# ethernet_switch.net
KiCad netlist of a schematic drawn in EAGLE
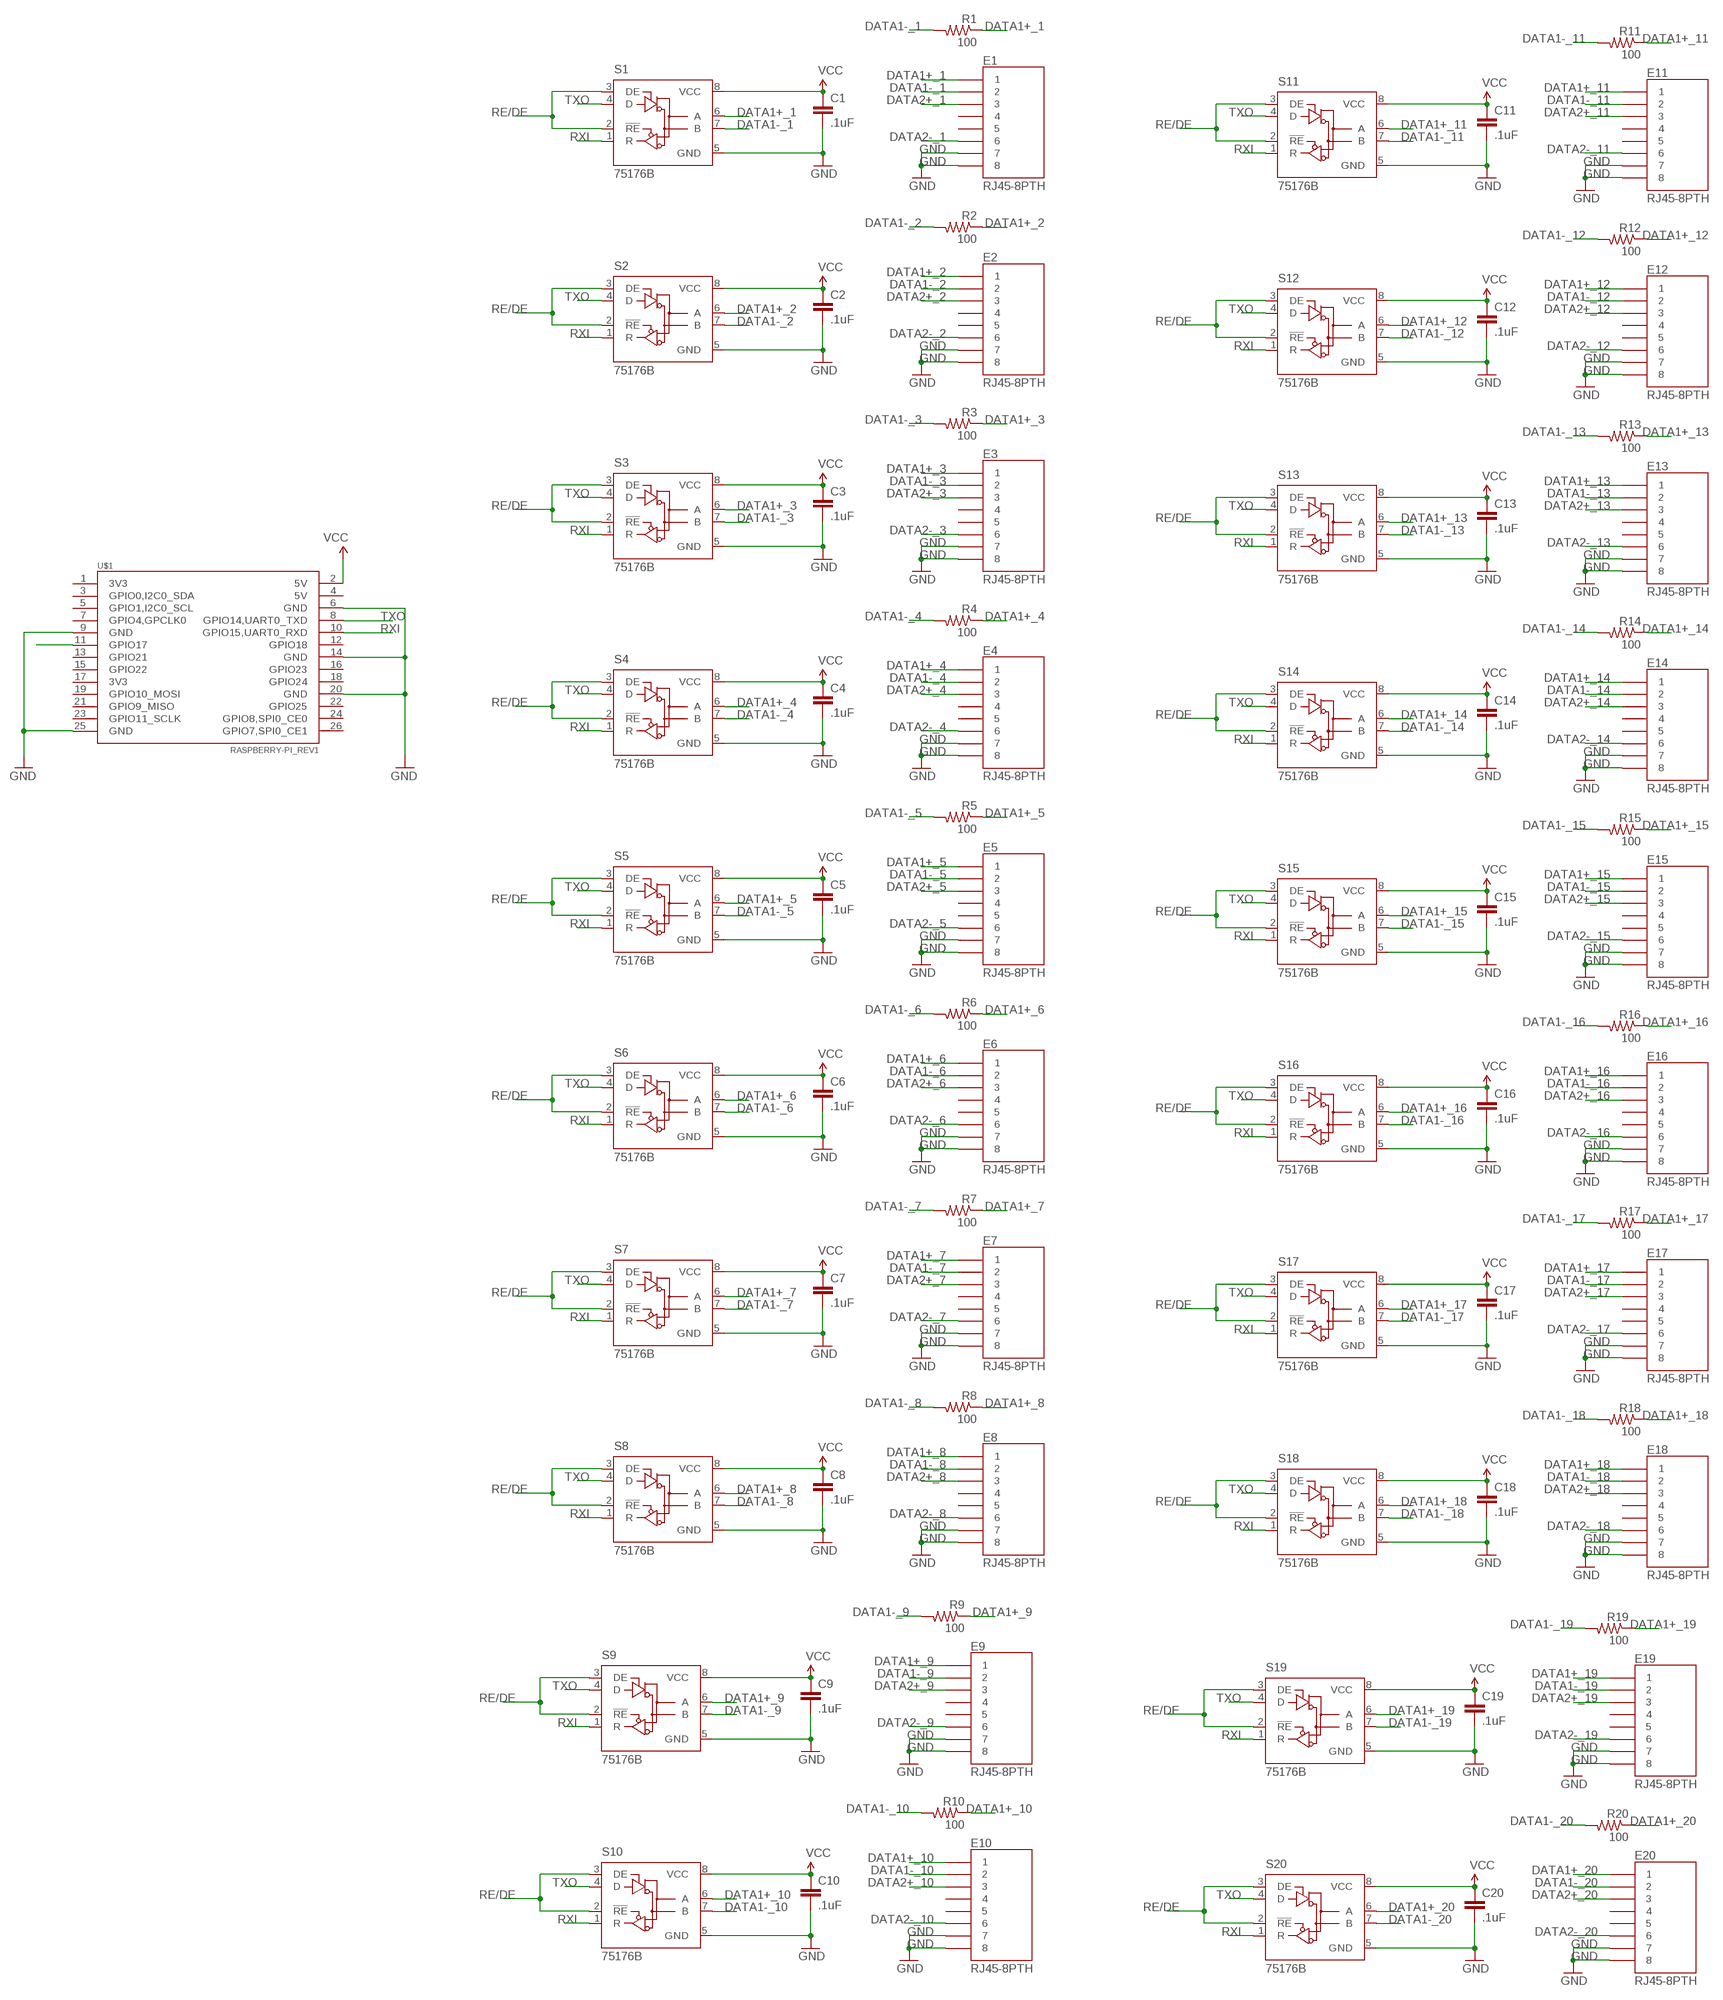
[diagram p0: schematic, sheet 1]

(export (version "E")
  (design (tool "Eeschema 10.0.6"))
  (components
    (comp (ref "C1")
      (value ".1uF")
      (footprint "eagle-import:0402-CAP")
      (libsource (lib "eagle-import") (part "CAP0402-CAP"))
    )
    (comp (ref "C2")
      (value ".1uF")
      (footprint "eagle-import:0402-CAP")
      (libsource (lib "eagle-import") (part "CAP0402-CAP"))
    )
    (comp (ref "C3")
      (value ".1uF")
      (footprint "eagle-import:0402-CAP")
      (libsource (lib "eagle-import") (part "CAP0402-CAP"))
    )
    (comp (ref "C4")
      (value ".1uF")
      (footprint "eagle-import:0402-CAP")
      (libsource (lib "eagle-import") (part "CAP0402-CAP"))
    )
    (comp (ref "C5")
      (value ".1uF")
      (footprint "eagle-import:0402-CAP")
      (libsource (lib "eagle-import") (part "CAP0402-CAP"))
    )
    (comp (ref "C6")
      (value ".1uF")
      (footprint "eagle-import:0402-CAP")
      (libsource (lib "eagle-import") (part "CAP0402-CAP"))
    )
    (comp (ref "C7")
      (value ".1uF")
      (footprint "eagle-import:0402-CAP")
      (libsource (lib "eagle-import") (part "CAP0402-CAP"))
    )
    (comp (ref "C8")
      (value ".1uF")
      (footprint "eagle-import:0402-CAP")
      (libsource (lib "eagle-import") (part "CAP0402-CAP"))
    )
    (comp (ref "C9")
      (value ".1uF")
      (footprint "eagle-import:0402-CAP")
      (libsource (lib "eagle-import") (part "CAP0402-CAP"))
    )
    (comp (ref "C10")
      (value ".1uF")
      (footprint "eagle-import:0402-CAP")
      (libsource (lib "eagle-import") (part "CAP0402-CAP"))
    )
    (comp (ref "C11")
      (value ".1uF")
      (footprint "eagle-import:0402-CAP")
      (libsource (lib "eagle-import") (part "CAP0402-CAP"))
    )
    (comp (ref "C12")
      (value ".1uF")
      (footprint "eagle-import:0402-CAP")
      (libsource (lib "eagle-import") (part "CAP0402-CAP"))
    )
    (comp (ref "C13")
      (value ".1uF")
      (footprint "eagle-import:0402-CAP")
      (libsource (lib "eagle-import") (part "CAP0402-CAP"))
    )
    (comp (ref "C14")
      (value ".1uF")
      (footprint "eagle-import:0402-CAP")
      (libsource (lib "eagle-import") (part "CAP0402-CAP"))
    )
    (comp (ref "C15")
      (value ".1uF")
      (footprint "eagle-import:0402-CAP")
      (libsource (lib "eagle-import") (part "CAP0402-CAP"))
    )
    (comp (ref "C16")
      (value ".1uF")
      (footprint "eagle-import:0402-CAP")
      (libsource (lib "eagle-import") (part "CAP0402-CAP"))
    )
    (comp (ref "C17")
      (value ".1uF")
      (footprint "eagle-import:0402-CAP")
      (libsource (lib "eagle-import") (part "CAP0402-CAP"))
    )
    (comp (ref "C18")
      (value ".1uF")
      (footprint "eagle-import:0402-CAP")
      (libsource (lib "eagle-import") (part "CAP0402-CAP"))
    )
    (comp (ref "C19")
      (value ".1uF")
      (footprint "eagle-import:0402-CAP")
      (libsource (lib "eagle-import") (part "CAP0402-CAP"))
    )
    (comp (ref "C20")
      (value ".1uF")
      (footprint "eagle-import:0402-CAP")
      (libsource (lib "eagle-import") (part "CAP0402-CAP"))
    )
    (comp (ref "E1")
      (value "RJ45-8PTH")
      (footprint "eagle-import:RJ45-8")
      (libsource (lib "eagle-import") (part "RJ45-8PTH"))
    )
    (comp (ref "E2")
      (value "RJ45-8PTH")
      (footprint "eagle-import:RJ45-8")
      (libsource (lib "eagle-import") (part "RJ45-8PTH"))
    )
    (comp (ref "E3")
      (value "RJ45-8PTH")
      (footprint "eagle-import:RJ45-8")
      (libsource (lib "eagle-import") (part "RJ45-8PTH"))
    )
    (comp (ref "E4")
      (value "RJ45-8PTH")
      (footprint "eagle-import:RJ45-8")
      (libsource (lib "eagle-import") (part "RJ45-8PTH"))
    )
    (comp (ref "E5")
      (value "RJ45-8PTH")
      (footprint "eagle-import:RJ45-8")
      (libsource (lib "eagle-import") (part "RJ45-8PTH"))
    )
    (comp (ref "E6")
      (value "RJ45-8PTH")
      (footprint "eagle-import:RJ45-8")
      (libsource (lib "eagle-import") (part "RJ45-8PTH"))
    )
    (comp (ref "E7")
      (value "RJ45-8PTH")
      (footprint "eagle-import:RJ45-8")
      (libsource (lib "eagle-import") (part "RJ45-8PTH"))
    )
    (comp (ref "E8")
      (value "RJ45-8PTH")
      (footprint "eagle-import:RJ45-8")
      (libsource (lib "eagle-import") (part "RJ45-8PTH"))
    )
    (comp (ref "E9")
      (value "RJ45-8PTH")
      (footprint "eagle-import:RJ45-8")
      (libsource (lib "eagle-import") (part "RJ45-8PTH"))
    )
    (comp (ref "E10")
      (value "RJ45-8PTH")
      (footprint "eagle-import:RJ45-8")
      (libsource (lib "eagle-import") (part "RJ45-8PTH"))
    )
    (comp (ref "E11")
      (value "RJ45-8PTH")
      (footprint "eagle-import:RJ45-8")
      (libsource (lib "eagle-import") (part "RJ45-8PTH"))
    )
    (comp (ref "E12")
      (value "RJ45-8PTH")
      (footprint "eagle-import:RJ45-8")
      (libsource (lib "eagle-import") (part "RJ45-8PTH"))
    )
    (comp (ref "E13")
      (value "RJ45-8PTH")
      (footprint "eagle-import:RJ45-8")
      (libsource (lib "eagle-import") (part "RJ45-8PTH"))
    )
    (comp (ref "E14")
      (value "RJ45-8PTH")
      (footprint "eagle-import:RJ45-8")
      (libsource (lib "eagle-import") (part "RJ45-8PTH"))
    )
    (comp (ref "E15")
      (value "RJ45-8PTH")
      (footprint "eagle-import:RJ45-8")
      (libsource (lib "eagle-import") (part "RJ45-8PTH"))
    )
    (comp (ref "E16")
      (value "RJ45-8PTH")
      (footprint "eagle-import:RJ45-8")
      (libsource (lib "eagle-import") (part "RJ45-8PTH"))
    )
    (comp (ref "E17")
      (value "RJ45-8PTH")
      (footprint "eagle-import:RJ45-8")
      (libsource (lib "eagle-import") (part "RJ45-8PTH"))
    )
    (comp (ref "E18")
      (value "RJ45-8PTH")
      (footprint "eagle-import:RJ45-8")
      (libsource (lib "eagle-import") (part "RJ45-8PTH"))
    )
    (comp (ref "E19")
      (value "RJ45-8PTH")
      (footprint "eagle-import:RJ45-8")
      (libsource (lib "eagle-import") (part "RJ45-8PTH"))
    )
    (comp (ref "E20")
      (value "RJ45-8PTH")
      (footprint "eagle-import:RJ45-8")
      (libsource (lib "eagle-import") (part "RJ45-8PTH"))
    )
    (comp (ref "R1")
      (value "100")
      (footprint "eagle-import:1206")
      (libsource (lib "eagle-import") (part "RESISTOR1206"))
    )
    (comp (ref "R2")
      (value "100")
      (footprint "eagle-import:1206")
      (libsource (lib "eagle-import") (part "RESISTOR1206"))
    )
    (comp (ref "R3")
      (value "100")
      (footprint "eagle-import:1206")
      (libsource (lib "eagle-import") (part "RESISTOR1206"))
    )
    (comp (ref "R4")
      (value "100")
      (footprint "eagle-import:1206")
      (libsource (lib "eagle-import") (part "RESISTOR1206"))
    )
    (comp (ref "R5")
      (value "100")
      (footprint "eagle-import:1206")
      (libsource (lib "eagle-import") (part "RESISTOR1206"))
    )
    (comp (ref "R6")
      (value "100")
      (footprint "eagle-import:1206")
      (libsource (lib "eagle-import") (part "RESISTOR1206"))
    )
    (comp (ref "R7")
      (value "100")
      (footprint "eagle-import:1206")
      (libsource (lib "eagle-import") (part "RESISTOR1206"))
    )
    (comp (ref "R8")
      (value "100")
      (footprint "eagle-import:1206")
      (libsource (lib "eagle-import") (part "RESISTOR1206"))
    )
    (comp (ref "R9")
      (value "100")
      (footprint "eagle-import:1206")
      (libsource (lib "eagle-import") (part "RESISTOR1206"))
    )
    (comp (ref "R10")
      (value "100")
      (footprint "eagle-import:1206")
      (libsource (lib "eagle-import") (part "RESISTOR1206"))
    )
    (comp (ref "R11")
      (value "100")
      (footprint "eagle-import:1206")
      (libsource (lib "eagle-import") (part "RESISTOR1206"))
    )
    (comp (ref "R12")
      (value "100")
      (footprint "eagle-import:1206")
      (libsource (lib "eagle-import") (part "RESISTOR1206"))
    )
    (comp (ref "R13")
      (value "100")
      (footprint "eagle-import:1206")
      (libsource (lib "eagle-import") (part "RESISTOR1206"))
    )
    (comp (ref "R14")
      (value "100")
      (footprint "eagle-import:1206")
      (libsource (lib "eagle-import") (part "RESISTOR1206"))
    )
    (comp (ref "R15")
      (value "100")
      (footprint "eagle-import:1206")
      (libsource (lib "eagle-import") (part "RESISTOR1206"))
    )
    (comp (ref "R16")
      (value "100")
      (footprint "eagle-import:1206")
      (libsource (lib "eagle-import") (part "RESISTOR1206"))
    )
    (comp (ref "R17")
      (value "100")
      (footprint "eagle-import:1206")
      (libsource (lib "eagle-import") (part "RESISTOR1206"))
    )
    (comp (ref "R18")
      (value "100")
      (footprint "eagle-import:1206")
      (libsource (lib "eagle-import") (part "RESISTOR1206"))
    )
    (comp (ref "R19")
      (value "100")
      (footprint "eagle-import:1206")
      (libsource (lib "eagle-import") (part "RESISTOR1206"))
    )
    (comp (ref "R20")
      (value "100")
      (footprint "eagle-import:1206")
      (libsource (lib "eagle-import") (part "RESISTOR1206"))
    )
    (comp (ref "S1")
      (value "75176B")
      (footprint "eagle-import:D_R-PDSO-G8")
      (libsource (lib "eagle-import") (part "75176B"))
    )
    (comp (ref "S2")
      (value "75176B")
      (footprint "eagle-import:D_R-PDSO-G8")
      (libsource (lib "eagle-import") (part "75176B"))
    )
    (comp (ref "S3")
      (value "75176B")
      (footprint "eagle-import:D_R-PDSO-G8")
      (libsource (lib "eagle-import") (part "75176B"))
    )
    (comp (ref "S4")
      (value "75176B")
      (footprint "eagle-import:D_R-PDSO-G8")
      (libsource (lib "eagle-import") (part "75176B"))
    )
    (comp (ref "S5")
      (value "75176B")
      (footprint "eagle-import:D_R-PDSO-G8")
      (libsource (lib "eagle-import") (part "75176B"))
    )
    (comp (ref "S6")
      (value "75176B")
      (footprint "eagle-import:D_R-PDSO-G8")
      (libsource (lib "eagle-import") (part "75176B"))
    )
    (comp (ref "S7")
      (value "75176B")
      (footprint "eagle-import:D_R-PDSO-G8")
      (libsource (lib "eagle-import") (part "75176B"))
    )
    (comp (ref "S8")
      (value "75176B")
      (footprint "eagle-import:D_R-PDSO-G8")
      (libsource (lib "eagle-import") (part "75176B"))
    )
    (comp (ref "S9")
      (value "75176B")
      (footprint "eagle-import:D_R-PDSO-G8")
      (libsource (lib "eagle-import") (part "75176B"))
    )
    (comp (ref "S10")
      (value "75176B")
      (footprint "eagle-import:D_R-PDSO-G8")
      (libsource (lib "eagle-import") (part "75176B"))
    )
    (comp (ref "S11")
      (value "75176B")
      (footprint "eagle-import:D_R-PDSO-G8")
      (libsource (lib "eagle-import") (part "75176B"))
    )
    (comp (ref "S12")
      (value "75176B")
      (footprint "eagle-import:D_R-PDSO-G8")
      (libsource (lib "eagle-import") (part "75176B"))
    )
    (comp (ref "S13")
      (value "75176B")
      (footprint "eagle-import:D_R-PDSO-G8")
      (libsource (lib "eagle-import") (part "75176B"))
    )
    (comp (ref "S14")
      (value "75176B")
      (footprint "eagle-import:D_R-PDSO-G8")
      (libsource (lib "eagle-import") (part "75176B"))
    )
    (comp (ref "S15")
      (value "75176B")
      (footprint "eagle-import:D_R-PDSO-G8")
      (libsource (lib "eagle-import") (part "75176B"))
    )
    (comp (ref "S16")
      (value "75176B")
      (footprint "eagle-import:D_R-PDSO-G8")
      (libsource (lib "eagle-import") (part "75176B"))
    )
    (comp (ref "S17")
      (value "75176B")
      (footprint "eagle-import:D_R-PDSO-G8")
      (libsource (lib "eagle-import") (part "75176B"))
    )
    (comp (ref "S18")
      (value "75176B")
      (footprint "eagle-import:D_R-PDSO-G8")
      (libsource (lib "eagle-import") (part "75176B"))
    )
    (comp (ref "S19")
      (value "75176B")
      (footprint "eagle-import:D_R-PDSO-G8")
      (libsource (lib "eagle-import") (part "75176B"))
    )
    (comp (ref "S20")
      (value "75176B")
      (footprint "eagle-import:D_R-PDSO-G8")
      (libsource (lib "eagle-import") (part "75176B"))
    )
    (comp (ref "U$1")
      (value "RASPBERRY-PI_REV1")
      (footprint "eagle-import:RASPBERRY-PI_REV1")
      (libsource (lib "eagle-import") (part "RASPBERRY-PI_REV1"))
    )
  )
  (nets
    (net (code "1") (name "/DATA1+_1") (class "Default")
      (node (ref "E1") (pin "1") (pinfunction "1_1") (pintype "bidirectional"))
      (node (ref "R1") (pin "1") (pinfunction "1_1") (pintype "passive"))
      (node (ref "S1") (pin "6") (pinfunction "A_6") (pintype "output"))
    )
    (net (code "2") (name "/DATA1+_2") (class "Default")
      (node (ref "E2") (pin "1") (pinfunction "1_1") (pintype "bidirectional"))
      (node (ref "R2") (pin "1") (pinfunction "1_1") (pintype "passive"))
      (node (ref "S2") (pin "6") (pinfunction "A_6") (pintype "output"))
    )
    (net (code "3") (name "/DATA1+_3") (class "Default")
      (node (ref "E3") (pin "1") (pinfunction "1_1") (pintype "bidirectional"))
      (node (ref "R3") (pin "1") (pinfunction "1_1") (pintype "passive"))
      (node (ref "S3") (pin "6") (pinfunction "A_6") (pintype "output"))
    )
    (net (code "4") (name "/DATA1+_4") (class "Default")
      (node (ref "E4") (pin "1") (pinfunction "1_1") (pintype "bidirectional"))
      (node (ref "R4") (pin "1") (pinfunction "1_1") (pintype "passive"))
      (node (ref "S4") (pin "6") (pinfunction "A_6") (pintype "output"))
    )
    (net (code "5") (name "/DATA1+_5") (class "Default")
      (node (ref "E5") (pin "1") (pinfunction "1_1") (pintype "bidirectional"))
      (node (ref "R5") (pin "1") (pinfunction "1_1") (pintype "passive"))
      (node (ref "S5") (pin "6") (pinfunction "A_6") (pintype "output"))
    )
    (net (code "6") (name "/DATA1+_6") (class "Default")
      (node (ref "E6") (pin "1") (pinfunction "1_1") (pintype "bidirectional"))
      (node (ref "R6") (pin "1") (pinfunction "1_1") (pintype "passive"))
      (node (ref "S6") (pin "6") (pinfunction "A_6") (pintype "output"))
    )
    (net (code "7") (name "/DATA1+_7") (class "Default")
      (node (ref "E7") (pin "1") (pinfunction "1_1") (pintype "bidirectional"))
      (node (ref "R7") (pin "1") (pinfunction "1_1") (pintype "passive"))
      (node (ref "S7") (pin "6") (pinfunction "A_6") (pintype "output"))
    )
    (net (code "8") (name "/DATA1+_8") (class "Default")
      (node (ref "E8") (pin "1") (pinfunction "1_1") (pintype "bidirectional"))
      (node (ref "R8") (pin "1") (pinfunction "1_1") (pintype "passive"))
      (node (ref "S8") (pin "6") (pinfunction "A_6") (pintype "output"))
    )
    (net (code "9") (name "/DATA1+_9") (class "Default")
      (node (ref "E9") (pin "1") (pinfunction "1_1") (pintype "bidirectional"))
      (node (ref "R9") (pin "1") (pinfunction "1_1") (pintype "passive"))
      (node (ref "S9") (pin "6") (pinfunction "A_6") (pintype "output"))
    )
    (net (code "10") (name "/DATA1+_10") (class "Default")
      (node (ref "E10") (pin "1") (pinfunction "1_1") (pintype "bidirectional"))
      (node (ref "R10") (pin "1") (pinfunction "1_1") (pintype "passive"))
      (node (ref "S10") (pin "6") (pinfunction "A_6") (pintype "output"))
    )
    (net (code "11") (name "/DATA1+_11") (class "Default")
      (node (ref "E11") (pin "1") (pinfunction "1_1") (pintype "bidirectional"))
      (node (ref "R11") (pin "1") (pinfunction "1_1") (pintype "passive"))
      (node (ref "S11") (pin "6") (pinfunction "A_6") (pintype "output"))
    )
    (net (code "12") (name "/DATA1+_12") (class "Default")
      (node (ref "E12") (pin "1") (pinfunction "1_1") (pintype "bidirectional"))
      (node (ref "R12") (pin "1") (pinfunction "1_1") (pintype "passive"))
      (node (ref "S12") (pin "6") (pinfunction "A_6") (pintype "output"))
    )
    (net (code "13") (name "/DATA1+_13") (class "Default")
      (node (ref "E13") (pin "1") (pinfunction "1_1") (pintype "bidirectional"))
      (node (ref "R13") (pin "1") (pinfunction "1_1") (pintype "passive"))
      (node (ref "S13") (pin "6") (pinfunction "A_6") (pintype "output"))
    )
    (net (code "14") (name "/DATA1+_14") (class "Default")
      (node (ref "E14") (pin "1") (pinfunction "1_1") (pintype "bidirectional"))
      (node (ref "R14") (pin "1") (pinfunction "1_1") (pintype "passive"))
      (node (ref "S14") (pin "6") (pinfunction "A_6") (pintype "output"))
    )
    (net (code "15") (name "/DATA1+_15") (class "Default")
      (node (ref "E15") (pin "1") (pinfunction "1_1") (pintype "bidirectional"))
      (node (ref "R15") (pin "1") (pinfunction "1_1") (pintype "passive"))
      (node (ref "S15") (pin "6") (pinfunction "A_6") (pintype "output"))
    )
    (net (code "16") (name "/DATA1+_16") (class "Default")
      (node (ref "E16") (pin "1") (pinfunction "1_1") (pintype "bidirectional"))
      (node (ref "R16") (pin "1") (pinfunction "1_1") (pintype "passive"))
      (node (ref "S16") (pin "6") (pinfunction "A_6") (pintype "output"))
    )
    (net (code "17") (name "/DATA1+_17") (class "Default")
      (node (ref "E17") (pin "1") (pinfunction "1_1") (pintype "bidirectional"))
      (node (ref "R17") (pin "1") (pinfunction "1_1") (pintype "passive"))
      (node (ref "S17") (pin "6") (pinfunction "A_6") (pintype "output"))
    )
    (net (code "18") (name "/DATA1+_18") (class "Default")
      (node (ref "E18") (pin "1") (pinfunction "1_1") (pintype "bidirectional"))
      (node (ref "R18") (pin "1") (pinfunction "1_1") (pintype "passive"))
      (node (ref "S18") (pin "6") (pinfunction "A_6") (pintype "output"))
    )
    (net (code "19") (name "/DATA1+_19") (class "Default")
      (node (ref "E19") (pin "1") (pinfunction "1_1") (pintype "bidirectional"))
      (node (ref "R19") (pin "1") (pinfunction "1_1") (pintype "passive"))
      (node (ref "S19") (pin "6") (pinfunction "A_6") (pintype "output"))
    )
    (net (code "20") (name "/DATA1+_20") (class "Default")
      (node (ref "E20") (pin "1") (pinfunction "1_1") (pintype "bidirectional"))
      (node (ref "R20") (pin "1") (pinfunction "1_1") (pintype "passive"))
      (node (ref "S20") (pin "6") (pinfunction "A_6") (pintype "output"))
    )
    (net (code "21") (name "/DATA1-_1") (class "Default")
      (node (ref "E1") (pin "2") (pinfunction "2_2") (pintype "bidirectional"))
      (node (ref "R1") (pin "2") (pinfunction "2_2") (pintype "passive"))
      (node (ref "S1") (pin "7") (pinfunction "B_7") (pintype "output"))
    )
    (net (code "22") (name "/DATA1-_2") (class "Default")
      (node (ref "E2") (pin "2") (pinfunction "2_2") (pintype "bidirectional"))
      (node (ref "R2") (pin "2") (pinfunction "2_2") (pintype "passive"))
      (node (ref "S2") (pin "7") (pinfunction "B_7") (pintype "output"))
    )
    (net (code "23") (name "/DATA1-_3") (class "Default")
      (node (ref "E3") (pin "2") (pinfunction "2_2") (pintype "bidirectional"))
      (node (ref "R3") (pin "2") (pinfunction "2_2") (pintype "passive"))
      (node (ref "S3") (pin "7") (pinfunction "B_7") (pintype "output"))
    )
    (net (code "24") (name "/DATA1-_4") (class "Default")
      (node (ref "E4") (pin "2") (pinfunction "2_2") (pintype "bidirectional"))
      (node (ref "R4") (pin "2") (pinfunction "2_2") (pintype "passive"))
      (node (ref "S4") (pin "7") (pinfunction "B_7") (pintype "output"))
    )
    (net (code "25") (name "/DATA1-_5") (class "Default")
      (node (ref "E5") (pin "2") (pinfunction "2_2") (pintype "bidirectional"))
      (node (ref "R5") (pin "2") (pinfunction "2_2") (pintype "passive"))
      (node (ref "S5") (pin "7") (pinfunction "B_7") (pintype "output"))
    )
    (net (code "26") (name "/DATA1-_6") (class "Default")
      (node (ref "E6") (pin "2") (pinfunction "2_2") (pintype "bidirectional"))
      (node (ref "R6") (pin "2") (pinfunction "2_2") (pintype "passive"))
      (node (ref "S6") (pin "7") (pinfunction "B_7") (pintype "output"))
    )
    (net (code "27") (name "/DATA1-_7") (class "Default")
      (node (ref "E7") (pin "2") (pinfunction "2_2") (pintype "bidirectional"))
      (node (ref "R7") (pin "2") (pinfunction "2_2") (pintype "passive"))
      (node (ref "S7") (pin "7") (pinfunction "B_7") (pintype "output"))
    )
    (net (code "28") (name "/DATA1-_8") (class "Default")
      (node (ref "E8") (pin "2") (pinfunction "2_2") (pintype "bidirectional"))
      (node (ref "R8") (pin "2") (pinfunction "2_2") (pintype "passive"))
      (node (ref "S8") (pin "7") (pinfunction "B_7") (pintype "output"))
    )
    (net (code "29") (name "/DATA1-_9") (class "Default")
      (node (ref "E9") (pin "2") (pinfunction "2_2") (pintype "bidirectional"))
      (node (ref "R9") (pin "2") (pinfunction "2_2") (pintype "passive"))
      (node (ref "S9") (pin "7") (pinfunction "B_7") (pintype "output"))
    )
    (net (code "30") (name "/DATA1-_10") (class "Default")
      (node (ref "E10") (pin "2") (pinfunction "2_2") (pintype "bidirectional"))
      (node (ref "R10") (pin "2") (pinfunction "2_2") (pintype "passive"))
      (node (ref "S10") (pin "7") (pinfunction "B_7") (pintype "output"))
    )
    (net (code "31") (name "/DATA1-_11") (class "Default")
      (node (ref "E11") (pin "2") (pinfunction "2_2") (pintype "bidirectional"))
      (node (ref "R11") (pin "2") (pinfunction "2_2") (pintype "passive"))
      (node (ref "S11") (pin "7") (pinfunction "B_7") (pintype "output"))
    )
    (net (code "32") (name "/DATA1-_12") (class "Default")
      (node (ref "E12") (pin "2") (pinfunction "2_2") (pintype "bidirectional"))
      (node (ref "R12") (pin "2") (pinfunction "2_2") (pintype "passive"))
      (node (ref "S12") (pin "7") (pinfunction "B_7") (pintype "output"))
    )
    (net (code "33") (name "/DATA1-_13") (class "Default")
      (node (ref "E13") (pin "2") (pinfunction "2_2") (pintype "bidirectional"))
      (node (ref "R13") (pin "2") (pinfunction "2_2") (pintype "passive"))
      (node (ref "S13") (pin "7") (pinfunction "B_7") (pintype "output"))
    )
    (net (code "34") (name "/DATA1-_14") (class "Default")
      (node (ref "E14") (pin "2") (pinfunction "2_2") (pintype "bidirectional"))
      (node (ref "R14") (pin "2") (pinfunction "2_2") (pintype "passive"))
      (node (ref "S14") (pin "7") (pinfunction "B_7") (pintype "output"))
    )
    (net (code "35") (name "/DATA1-_15") (class "Default")
      (node (ref "E15") (pin "2") (pinfunction "2_2") (pintype "bidirectional"))
      (node (ref "R15") (pin "2") (pinfunction "2_2") (pintype "passive"))
      (node (ref "S15") (pin "7") (pinfunction "B_7") (pintype "output"))
    )
    (net (code "36") (name "/DATA1-_16") (class "Default")
      (node (ref "E16") (pin "2") (pinfunction "2_2") (pintype "bidirectional"))
      (node (ref "R16") (pin "2") (pinfunction "2_2") (pintype "passive"))
      (node (ref "S16") (pin "7") (pinfunction "B_7") (pintype "output"))
    )
    (net (code "37") (name "/DATA1-_17") (class "Default")
      (node (ref "E17") (pin "2") (pinfunction "2_2") (pintype "bidirectional"))
      (node (ref "R17") (pin "2") (pinfunction "2_2") (pintype "passive"))
      (node (ref "S17") (pin "7") (pinfunction "B_7") (pintype "output"))
    )
    (net (code "38") (name "/DATA1-_18") (class "Default")
      (node (ref "E18") (pin "2") (pinfunction "2_2") (pintype "bidirectional"))
      (node (ref "R18") (pin "2") (pinfunction "2_2") (pintype "passive"))
      (node (ref "S18") (pin "7") (pinfunction "B_7") (pintype "output"))
    )
    (net (code "39") (name "/DATA1-_19") (class "Default")
      (node (ref "E19") (pin "2") (pinfunction "2_2") (pintype "bidirectional"))
      (node (ref "R19") (pin "2") (pinfunction "2_2") (pintype "passive"))
      (node (ref "S19") (pin "7") (pinfunction "B_7") (pintype "output"))
    )
    (net (code "40") (name "/DATA1-_20") (class "Default")
      (node (ref "E20") (pin "2") (pinfunction "2_2") (pintype "bidirectional"))
      (node (ref "R20") (pin "2") (pinfunction "2_2") (pintype "passive"))
      (node (ref "S20") (pin "7") (pinfunction "B_7") (pintype "output"))
    )
    (net (code "41") (name "/DATA2+_1") (class "Default")
      (node (ref "E1") (pin "3") (pinfunction "3_3") (pintype "bidirectional"))
    )
    (net (code "42") (name "/DATA2+_2") (class "Default")
      (node (ref "E2") (pin "3") (pinfunction "3_3") (pintype "bidirectional"))
    )
    (net (code "43") (name "/DATA2+_3") (class "Default")
      (node (ref "E3") (pin "3") (pinfunction "3_3") (pintype "bidirectional"))
    )
    (net (code "44") (name "/DATA2+_4") (class "Default")
      (node (ref "E4") (pin "3") (pinfunction "3_3") (pintype "bidirectional"))
    )
    (net (code "45") (name "/DATA2+_5") (class "Default")
      (node (ref "E5") (pin "3") (pinfunction "3_3") (pintype "bidirectional"))
    )
    (net (code "46") (name "/DATA2+_6") (class "Default")
      (node (ref "E6") (pin "3") (pinfunction "3_3") (pintype "bidirectional"))
    )
    (net (code "47") (name "/DATA2+_7") (class "Default")
      (node (ref "E7") (pin "3") (pinfunction "3_3") (pintype "bidirectional"))
    )
    (net (code "48") (name "/DATA2+_8") (class "Default")
      (node (ref "E8") (pin "3") (pinfunction "3_3") (pintype "bidirectional"))
    )
    (net (code "49") (name "/DATA2+_9") (class "Default")
      (node (ref "E9") (pin "3") (pinfunction "3_3") (pintype "bidirectional"))
    )
    (net (code "50") (name "/DATA2+_10") (class "Default")
      (node (ref "E10") (pin "3") (pinfunction "3_3") (pintype "bidirectional"))
    )
    (net (code "51") (name "/DATA2+_11") (class "Default")
      (node (ref "E11") (pin "3") (pinfunction "3_3") (pintype "bidirectional"))
    )
    (net (code "52") (name "/DATA2+_12") (class "Default")
      (node (ref "E12") (pin "3") (pinfunction "3_3") (pintype "bidirectional"))
    )
    (net (code "53") (name "/DATA2+_13") (class "Default")
      (node (ref "E13") (pin "3") (pinfunction "3_3") (pintype "bidirectional"))
    )
    (net (code "54") (name "/DATA2+_14") (class "Default")
      (node (ref "E14") (pin "3") (pinfunction "3_3") (pintype "bidirectional"))
    )
    (net (code "55") (name "/DATA2+_15") (class "Default")
      (node (ref "E15") (pin "3") (pinfunction "3_3") (pintype "bidirectional"))
    )
    (net (code "56") (name "/DATA2+_16") (class "Default")
      (node (ref "E16") (pin "3") (pinfunction "3_3") (pintype "bidirectional"))
    )
    (net (code "57") (name "/DATA2+_17") (class "Default")
      (node (ref "E17") (pin "3") (pinfunction "3_3") (pintype "bidirectional"))
    )
    (net (code "58") (name "/DATA2+_18") (class "Default")
      (node (ref "E18") (pin "3") (pinfunction "3_3") (pintype "bidirectional"))
    )
    (net (code "59") (name "/DATA2+_19") (class "Default")
      (node (ref "E19") (pin "3") (pinfunction "3_3") (pintype "bidirectional"))
    )
    (net (code "60") (name "/DATA2+_20") (class "Default")
      (node (ref "E20") (pin "3") (pinfunction "3_3") (pintype "bidirectional"))
    )
    (net (code "61") (name "/DATA2-_1") (class "Default")
      (node (ref "E1") (pin "6") (pinfunction "6_6") (pintype "bidirectional"))
    )
    (net (code "62") (name "/DATA2-_2") (class "Default")
      (node (ref "E2") (pin "6") (pinfunction "6_6") (pintype "bidirectional"))
    )
    (net (code "63") (name "/DATA2-_3") (class "Default")
      (node (ref "E3") (pin "6") (pinfunction "6_6") (pintype "bidirectional"))
    )
    (net (code "64") (name "/DATA2-_4") (class "Default")
      (node (ref "E4") (pin "6") (pinfunction "6_6") (pintype "bidirectional"))
    )
    (net (code "65") (name "/DATA2-_5") (class "Default")
      (node (ref "E5") (pin "6") (pinfunction "6_6") (pintype "bidirectional"))
    )
    (net (code "66") (name "/DATA2-_6") (class "Default")
      (node (ref "E6") (pin "6") (pinfunction "6_6") (pintype "bidirectional"))
    )
    (net (code "67") (name "/DATA2-_7") (class "Default")
      (node (ref "E7") (pin "6") (pinfunction "6_6") (pintype "bidirectional"))
    )
    (net (code "68") (name "/DATA2-_8") (class "Default")
      (node (ref "E8") (pin "6") (pinfunction "6_6") (pintype "bidirectional"))
    )
    (net (code "69") (name "/DATA2-_9") (class "Default")
      (node (ref "E9") (pin "6") (pinfunction "6_6") (pintype "bidirectional"))
    )
    (net (code "70") (name "/DATA2-_10") (class "Default")
      (node (ref "E10") (pin "6") (pinfunction "6_6") (pintype "bidirectional"))
    )
    (net (code "71") (name "/DATA2-_11") (class "Default")
      (node (ref "E11") (pin "6") (pinfunction "6_6") (pintype "bidirectional"))
    )
    (net (code "72") (name "/DATA2-_12") (class "Default")
      (node (ref "E12") (pin "6") (pinfunction "6_6") (pintype "bidirectional"))
    )
    (net (code "73") (name "/DATA2-_13") (class "Default")
      (node (ref "E13") (pin "6") (pinfunction "6_6") (pintype "bidirectional"))
    )
    (net (code "74") (name "/DATA2-_14") (class "Default")
      (node (ref "E14") (pin "6") (pinfunction "6_6") (pintype "bidirectional"))
    )
    (net (code "75") (name "/DATA2-_15") (class "Default")
      (node (ref "E15") (pin "6") (pinfunction "6_6") (pintype "bidirectional"))
    )
    (net (code "76") (name "/DATA2-_16") (class "Default")
      (node (ref "E16") (pin "6") (pinfunction "6_6") (pintype "bidirectional"))
    )
    (net (code "77") (name "/DATA2-_17") (class "Default")
      (node (ref "E17") (pin "6") (pinfunction "6_6") (pintype "bidirectional"))
    )
    (net (code "78") (name "/DATA2-_18") (class "Default")
      (node (ref "E18") (pin "6") (pinfunction "6_6") (pintype "bidirectional"))
    )
    (net (code "79") (name "/DATA2-_19") (class "Default")
      (node (ref "E19") (pin "6") (pinfunction "6_6") (pintype "bidirectional"))
    )
    (net (code "80") (name "/DATA2-_20") (class "Default")
      (node (ref "E20") (pin "6") (pinfunction "6_6") (pintype "bidirectional"))
    )
    (net (code "81") (name "/RE{slash}DE") (class "Default")
      (node (ref "S1") (pin "2") (pinfunction "~{RE}_2") (pintype "input"))
      (node (ref "S1") (pin "3") (pinfunction "DE_3") (pintype "input"))
      (node (ref "S10") (pin "2") (pinfunction "~{RE}_2") (pintype "input"))
      (node (ref "S10") (pin "3") (pinfunction "DE_3") (pintype "input"))
      (node (ref "S11") (pin "2") (pinfunction "~{RE}_2") (pintype "input"))
      (node (ref "S11") (pin "3") (pinfunction "DE_3") (pintype "input"))
      (node (ref "S12") (pin "2") (pinfunction "~{RE}_2") (pintype "input"))
      (node (ref "S12") (pin "3") (pinfunction "DE_3") (pintype "input"))
      (node (ref "S13") (pin "2") (pinfunction "~{RE}_2") (pintype "input"))
      (node (ref "S13") (pin "3") (pinfunction "DE_3") (pintype "input"))
      (node (ref "S14") (pin "2") (pinfunction "~{RE}_2") (pintype "input"))
      (node (ref "S14") (pin "3") (pinfunction "DE_3") (pintype "input"))
      (node (ref "S15") (pin "2") (pinfunction "~{RE}_2") (pintype "input"))
      (node (ref "S15") (pin "3") (pinfunction "DE_3") (pintype "input"))
      (node (ref "S16") (pin "2") (pinfunction "~{RE}_2") (pintype "input"))
      (node (ref "S16") (pin "3") (pinfunction "DE_3") (pintype "input"))
      (node (ref "S17") (pin "2") (pinfunction "~{RE}_2") (pintype "input"))
      (node (ref "S17") (pin "3") (pinfunction "DE_3") (pintype "input"))
      (node (ref "S18") (pin "2") (pinfunction "~{RE}_2") (pintype "input"))
      (node (ref "S18") (pin "3") (pinfunction "DE_3") (pintype "input"))
      (node (ref "S19") (pin "2") (pinfunction "~{RE}_2") (pintype "input"))
      (node (ref "S19") (pin "3") (pinfunction "DE_3") (pintype "input"))
      (node (ref "S2") (pin "2") (pinfunction "~{RE}_2") (pintype "input"))
      (node (ref "S2") (pin "3") (pinfunction "DE_3") (pintype "input"))
      (node (ref "S20") (pin "2") (pinfunction "~{RE}_2") (pintype "input"))
      (node (ref "S20") (pin "3") (pinfunction "DE_3") (pintype "input"))
      (node (ref "S3") (pin "2") (pinfunction "~{RE}_2") (pintype "input"))
      (node (ref "S3") (pin "3") (pinfunction "DE_3") (pintype "input"))
      (node (ref "S4") (pin "2") (pinfunction "~{RE}_2") (pintype "input"))
      (node (ref "S4") (pin "3") (pinfunction "DE_3") (pintype "input"))
      (node (ref "S5") (pin "2") (pinfunction "~{RE}_2") (pintype "input"))
      (node (ref "S5") (pin "3") (pinfunction "DE_3") (pintype "input"))
      (node (ref "S6") (pin "2") (pinfunction "~{RE}_2") (pintype "input"))
      (node (ref "S6") (pin "3") (pinfunction "DE_3") (pintype "input"))
      (node (ref "S7") (pin "2") (pinfunction "~{RE}_2") (pintype "input"))
      (node (ref "S7") (pin "3") (pinfunction "DE_3") (pintype "input"))
      (node (ref "S8") (pin "2") (pinfunction "~{RE}_2") (pintype "input"))
      (node (ref "S8") (pin "3") (pinfunction "DE_3") (pintype "input"))
      (node (ref "S9") (pin "2") (pinfunction "~{RE}_2") (pintype "input"))
      (node (ref "S9") (pin "3") (pinfunction "DE_3") (pintype "input"))
      (node (ref "U$1") (pin "11") (pinfunction "GPIO17_11") (pintype "bidirectional"))
    )
    (net (code "82") (name "/RXI") (class "Default")
      (node (ref "S1") (pin "1") (pinfunction "R_1") (pintype "input"))
      (node (ref "S10") (pin "1") (pinfunction "R_1") (pintype "input"))
      (node (ref "S11") (pin "1") (pinfunction "R_1") (pintype "input"))
      (node (ref "S12") (pin "1") (pinfunction "R_1") (pintype "input"))
      (node (ref "S13") (pin "1") (pinfunction "R_1") (pintype "input"))
      (node (ref "S14") (pin "1") (pinfunction "R_1") (pintype "input"))
      (node (ref "S15") (pin "1") (pinfunction "R_1") (pintype "input"))
      (node (ref "S16") (pin "1") (pinfunction "R_1") (pintype "input"))
      (node (ref "S17") (pin "1") (pinfunction "R_1") (pintype "input"))
      (node (ref "S18") (pin "1") (pinfunction "R_1") (pintype "input"))
      (node (ref "S19") (pin "1") (pinfunction "R_1") (pintype "input"))
      (node (ref "S2") (pin "1") (pinfunction "R_1") (pintype "input"))
      (node (ref "S20") (pin "1") (pinfunction "R_1") (pintype "input"))
      (node (ref "S3") (pin "1") (pinfunction "R_1") (pintype "input"))
      (node (ref "S4") (pin "1") (pinfunction "R_1") (pintype "input"))
      (node (ref "S5") (pin "1") (pinfunction "R_1") (pintype "input"))
      (node (ref "S6") (pin "1") (pinfunction "R_1") (pintype "input"))
      (node (ref "S7") (pin "1") (pinfunction "R_1") (pintype "input"))
      (node (ref "S8") (pin "1") (pinfunction "R_1") (pintype "input"))
      (node (ref "S9") (pin "1") (pinfunction "R_1") (pintype "input"))
      (node (ref "U$1") (pin "10") (pinfunction "GPIO15,UART0_RXD_10") (pintype "bidirectional"))
    )
    (net (code "83") (name "/TXO") (class "Default")
      (node (ref "S1") (pin "4") (pinfunction "D_4") (pintype "input"))
      (node (ref "S10") (pin "4") (pinfunction "D_4") (pintype "input"))
      (node (ref "S11") (pin "4") (pinfunction "D_4") (pintype "input"))
      (node (ref "S12") (pin "4") (pinfunction "D_4") (pintype "input"))
      (node (ref "S13") (pin "4") (pinfunction "D_4") (pintype "input"))
      (node (ref "S14") (pin "4") (pinfunction "D_4") (pintype "input"))
      (node (ref "S15") (pin "4") (pinfunction "D_4") (pintype "input"))
      (node (ref "S16") (pin "4") (pinfunction "D_4") (pintype "input"))
      (node (ref "S17") (pin "4") (pinfunction "D_4") (pintype "input"))
      (node (ref "S18") (pin "4") (pinfunction "D_4") (pintype "input"))
      (node (ref "S19") (pin "4") (pinfunction "D_4") (pintype "input"))
      (node (ref "S2") (pin "4") (pinfunction "D_4") (pintype "input"))
      (node (ref "S20") (pin "4") (pinfunction "D_4") (pintype "input"))
      (node (ref "S3") (pin "4") (pinfunction "D_4") (pintype "input"))
      (node (ref "S4") (pin "4") (pinfunction "D_4") (pintype "input"))
      (node (ref "S5") (pin "4") (pinfunction "D_4") (pintype "input"))
      (node (ref "S6") (pin "4") (pinfunction "D_4") (pintype "input"))
      (node (ref "S7") (pin "4") (pinfunction "D_4") (pintype "input"))
      (node (ref "S8") (pin "4") (pinfunction "D_4") (pintype "input"))
      (node (ref "S9") (pin "4") (pinfunction "D_4") (pintype "input"))
      (node (ref "U$1") (pin "8") (pinfunction "GPIO14,UART0_TXD_8") (pintype "bidirectional"))
    )
    (net (code "84") (name "GND") (class "Default")
      (node (ref "C1") (pin "2") (pinfunction "2_2") (pintype "passive"))
      (node (ref "C10") (pin "2") (pinfunction "2_2") (pintype "passive"))
      (node (ref "C11") (pin "2") (pinfunction "2_2") (pintype "passive"))
      (node (ref "C12") (pin "2") (pinfunction "2_2") (pintype "passive"))
      (node (ref "C13") (pin "2") (pinfunction "2_2") (pintype "passive"))
      (node (ref "C14") (pin "2") (pinfunction "2_2") (pintype "passive"))
      (node (ref "C15") (pin "2") (pinfunction "2_2") (pintype "passive"))
      (node (ref "C16") (pin "2") (pinfunction "2_2") (pintype "passive"))
      (node (ref "C17") (pin "2") (pinfunction "2_2") (pintype "passive"))
      (node (ref "C18") (pin "2") (pinfunction "2_2") (pintype "passive"))
      (node (ref "C19") (pin "2") (pinfunction "2_2") (pintype "passive"))
      (node (ref "C2") (pin "2") (pinfunction "2_2") (pintype "passive"))
      (node (ref "C20") (pin "2") (pinfunction "2_2") (pintype "passive"))
      (node (ref "C3") (pin "2") (pinfunction "2_2") (pintype "passive"))
      (node (ref "C4") (pin "2") (pinfunction "2_2") (pintype "passive"))
      (node (ref "C5") (pin "2") (pinfunction "2_2") (pintype "passive"))
      (node (ref "C6") (pin "2") (pinfunction "2_2") (pintype "passive"))
      (node (ref "C7") (pin "2") (pinfunction "2_2") (pintype "passive"))
      (node (ref "C8") (pin "2") (pinfunction "2_2") (pintype "passive"))
      (node (ref "C9") (pin "2") (pinfunction "2_2") (pintype "passive"))
      (node (ref "E1") (pin "7") (pinfunction "7_7") (pintype "bidirectional"))
      (node (ref "E1") (pin "8") (pinfunction "8_8") (pintype "bidirectional"))
      (node (ref "E10") (pin "7") (pinfunction "7_7") (pintype "bidirectional"))
      (node (ref "E10") (pin "8") (pinfunction "8_8") (pintype "bidirectional"))
      (node (ref "E11") (pin "7") (pinfunction "7_7") (pintype "bidirectional"))
      (node (ref "E11") (pin "8") (pinfunction "8_8") (pintype "bidirectional"))
      (node (ref "E12") (pin "7") (pinfunction "7_7") (pintype "bidirectional"))
      (node (ref "E12") (pin "8") (pinfunction "8_8") (pintype "bidirectional"))
      (node (ref "E13") (pin "7") (pinfunction "7_7") (pintype "bidirectional"))
      (node (ref "E13") (pin "8") (pinfunction "8_8") (pintype "bidirectional"))
      (node (ref "E14") (pin "7") (pinfunction "7_7") (pintype "bidirectional"))
      (node (ref "E14") (pin "8") (pinfunction "8_8") (pintype "bidirectional"))
      (node (ref "E15") (pin "7") (pinfunction "7_7") (pintype "bidirectional"))
      (node (ref "E15") (pin "8") (pinfunction "8_8") (pintype "bidirectional"))
      (node (ref "E16") (pin "7") (pinfunction "7_7") (pintype "bidirectional"))
      (node (ref "E16") (pin "8") (pinfunction "8_8") (pintype "bidirectional"))
      (node (ref "E17") (pin "7") (pinfunction "7_7") (pintype "bidirectional"))
      (node (ref "E17") (pin "8") (pinfunction "8_8") (pintype "bidirectional"))
      (node (ref "E18") (pin "7") (pinfunction "7_7") (pintype "bidirectional"))
      (node (ref "E18") (pin "8") (pinfunction "8_8") (pintype "bidirectional"))
      (node (ref "E19") (pin "7") (pinfunction "7_7") (pintype "bidirectional"))
      (node (ref "E19") (pin "8") (pinfunction "8_8") (pintype "bidirectional"))
      (node (ref "E2") (pin "7") (pinfunction "7_7") (pintype "bidirectional"))
      (node (ref "E2") (pin "8") (pinfunction "8_8") (pintype "bidirectional"))
      (node (ref "E20") (pin "7") (pinfunction "7_7") (pintype "bidirectional"))
      (node (ref "E20") (pin "8") (pinfunction "8_8") (pintype "bidirectional"))
      (node (ref "E3") (pin "7") (pinfunction "7_7") (pintype "bidirectional"))
      (node (ref "E3") (pin "8") (pinfunction "8_8") (pintype "bidirectional"))
      (node (ref "E4") (pin "7") (pinfunction "7_7") (pintype "bidirectional"))
      (node (ref "E4") (pin "8") (pinfunction "8_8") (pintype "bidirectional"))
      (node (ref "E5") (pin "7") (pinfunction "7_7") (pintype "bidirectional"))
      (node (ref "E5") (pin "8") (pinfunction "8_8") (pintype "bidirectional"))
      (node (ref "E6") (pin "7") (pinfunction "7_7") (pintype "bidirectional"))
      (node (ref "E6") (pin "8") (pinfunction "8_8") (pintype "bidirectional"))
      (node (ref "E7") (pin "7") (pinfunction "7_7") (pintype "bidirectional"))
      (node (ref "E7") (pin "8") (pinfunction "8_8") (pintype "bidirectional"))
      (node (ref "E8") (pin "7") (pinfunction "7_7") (pintype "bidirectional"))
      (node (ref "E8") (pin "8") (pinfunction "8_8") (pintype "bidirectional"))
      (node (ref "E9") (pin "7") (pinfunction "7_7") (pintype "bidirectional"))
      (node (ref "E9") (pin "8") (pinfunction "8_8") (pintype "bidirectional"))
      (node (ref "S1") (pin "5") (pinfunction "GND_5") (pintype "power_in"))
      (node (ref "S10") (pin "5") (pinfunction "GND_5") (pintype "power_in"))
      (node (ref "S11") (pin "5") (pinfunction "GND_5") (pintype "power_in"))
      (node (ref "S12") (pin "5") (pinfunction "GND_5") (pintype "power_in"))
      (node (ref "S13") (pin "5") (pinfunction "GND_5") (pintype "power_in"))
      (node (ref "S14") (pin "5") (pinfunction "GND_5") (pintype "power_in"))
      (node (ref "S15") (pin "5") (pinfunction "GND_5") (pintype "power_in"))
      (node (ref "S16") (pin "5") (pinfunction "GND_5") (pintype "power_in"))
      (node (ref "S17") (pin "5") (pinfunction "GND_5") (pintype "power_in"))
      (node (ref "S18") (pin "5") (pinfunction "GND_5") (pintype "power_in"))
      (node (ref "S19") (pin "5") (pinfunction "GND_5") (pintype "power_in"))
      (node (ref "S2") (pin "5") (pinfunction "GND_5") (pintype "power_in"))
      (node (ref "S20") (pin "5") (pinfunction "GND_5") (pintype "power_in"))
      (node (ref "S3") (pin "5") (pinfunction "GND_5") (pintype "power_in"))
      (node (ref "S4") (pin "5") (pinfunction "GND_5") (pintype "power_in"))
      (node (ref "S5") (pin "5") (pinfunction "GND_5") (pintype "power_in"))
      (node (ref "S6") (pin "5") (pinfunction "GND_5") (pintype "power_in"))
      (node (ref "S7") (pin "5") (pinfunction "GND_5") (pintype "power_in"))
      (node (ref "S8") (pin "5") (pinfunction "GND_5") (pintype "power_in"))
      (node (ref "S9") (pin "5") (pinfunction "GND_5") (pintype "power_in"))
      (node (ref "U$1") (pin "14") (pinfunction "GND_14") (pintype "bidirectional"))
      (node (ref "U$1") (pin "20") (pinfunction "GND_20") (pintype "bidirectional"))
      (node (ref "U$1") (pin "25") (pinfunction "GND_25") (pintype "bidirectional"))
      (node (ref "U$1") (pin "6") (pinfunction "GND_6") (pintype "bidirectional"))
      (node (ref "U$1") (pin "9") (pinfunction "GND_9") (pintype "bidirectional"))
    )
    (net (code "85") (name "VCC") (class "Default")
      (node (ref "C1") (pin "1") (pinfunction "1_1") (pintype "passive"))
      (node (ref "C10") (pin "1") (pinfunction "1_1") (pintype "passive"))
      (node (ref "C11") (pin "1") (pinfunction "1_1") (pintype "passive"))
      (node (ref "C12") (pin "1") (pinfunction "1_1") (pintype "passive"))
      (node (ref "C13") (pin "1") (pinfunction "1_1") (pintype "passive"))
      (node (ref "C14") (pin "1") (pinfunction "1_1") (pintype "passive"))
      (node (ref "C15") (pin "1") (pinfunction "1_1") (pintype "passive"))
      (node (ref "C16") (pin "1") (pinfunction "1_1") (pintype "passive"))
      (node (ref "C17") (pin "1") (pinfunction "1_1") (pintype "passive"))
      (node (ref "C18") (pin "1") (pinfunction "1_1") (pintype "passive"))
      (node (ref "C19") (pin "1") (pinfunction "1_1") (pintype "passive"))
      (node (ref "C2") (pin "1") (pinfunction "1_1") (pintype "passive"))
      (node (ref "C20") (pin "1") (pinfunction "1_1") (pintype "passive"))
      (node (ref "C3") (pin "1") (pinfunction "1_1") (pintype "passive"))
      (node (ref "C4") (pin "1") (pinfunction "1_1") (pintype "passive"))
      (node (ref "C5") (pin "1") (pinfunction "1_1") (pintype "passive"))
      (node (ref "C6") (pin "1") (pinfunction "1_1") (pintype "passive"))
      (node (ref "C7") (pin "1") (pinfunction "1_1") (pintype "passive"))
      (node (ref "C8") (pin "1") (pinfunction "1_1") (pintype "passive"))
      (node (ref "C9") (pin "1") (pinfunction "1_1") (pintype "passive"))
      (node (ref "S1") (pin "8") (pinfunction "VCC_8") (pintype "power_in"))
      (node (ref "S10") (pin "8") (pinfunction "VCC_8") (pintype "power_in"))
      (node (ref "S11") (pin "8") (pinfunction "VCC_8") (pintype "power_in"))
      (node (ref "S12") (pin "8") (pinfunction "VCC_8") (pintype "power_in"))
      (node (ref "S13") (pin "8") (pinfunction "VCC_8") (pintype "power_in"))
      (node (ref "S14") (pin "8") (pinfunction "VCC_8") (pintype "power_in"))
      (node (ref "S15") (pin "8") (pinfunction "VCC_8") (pintype "power_in"))
      (node (ref "S16") (pin "8") (pinfunction "VCC_8") (pintype "power_in"))
      (node (ref "S17") (pin "8") (pinfunction "VCC_8") (pintype "power_in"))
      (node (ref "S18") (pin "8") (pinfunction "VCC_8") (pintype "power_in"))
      (node (ref "S19") (pin "8") (pinfunction "VCC_8") (pintype "power_in"))
      (node (ref "S2") (pin "8") (pinfunction "VCC_8") (pintype "power_in"))
      (node (ref "S20") (pin "8") (pinfunction "VCC_8") (pintype "power_in"))
      (node (ref "S3") (pin "8") (pinfunction "VCC_8") (pintype "power_in"))
      (node (ref "S4") (pin "8") (pinfunction "VCC_8") (pintype "power_in"))
      (node (ref "S5") (pin "8") (pinfunction "VCC_8") (pintype "power_in"))
      (node (ref "S6") (pin "8") (pinfunction "VCC_8") (pintype "power_in"))
      (node (ref "S7") (pin "8") (pinfunction "VCC_8") (pintype "power_in"))
      (node (ref "S8") (pin "8") (pinfunction "VCC_8") (pintype "power_in"))
      (node (ref "S9") (pin "8") (pinfunction "VCC_8") (pintype "power_in"))
      (node (ref "U$1") (pin "2") (pinfunction "5V_2") (pintype "bidirectional"))
    )
    (net (code "86") (name "unconnected-(E1-Pad4)") (class "Default")
      (node (ref "E1") (pin "4") (pinfunction "4_4") (pintype "bidirectional"))
    )
    (net (code "87") (name "unconnected-(E1-Pad5)") (class "Default")
      (node (ref "E1") (pin "5") (pinfunction "5_5") (pintype "bidirectional"))
    )
    (net (code "88") (name "unconnected-(E2-Pad4)") (class "Default")
      (node (ref "E2") (pin "4") (pinfunction "4_4") (pintype "bidirectional"))
    )
    (net (code "89") (name "unconnected-(E2-Pad5)") (class "Default")
      (node (ref "E2") (pin "5") (pinfunction "5_5") (pintype "bidirectional"))
    )
    (net (code "90") (name "unconnected-(E3-Pad4)") (class "Default")
      (node (ref "E3") (pin "4") (pinfunction "4_4") (pintype "bidirectional"))
    )
    (net (code "91") (name "unconnected-(E3-Pad5)") (class "Default")
      (node (ref "E3") (pin "5") (pinfunction "5_5") (pintype "bidirectional"))
    )
    (net (code "92") (name "unconnected-(E4-Pad4)") (class "Default")
      (node (ref "E4") (pin "4") (pinfunction "4_4") (pintype "bidirectional"))
    )
    (net (code "93") (name "unconnected-(E4-Pad5)") (class "Default")
      (node (ref "E4") (pin "5") (pinfunction "5_5") (pintype "bidirectional"))
    )
    (net (code "94") (name "unconnected-(E5-Pad4)") (class "Default")
      (node (ref "E5") (pin "4") (pinfunction "4_4") (pintype "bidirectional"))
    )
    (net (code "95") (name "unconnected-(E5-Pad5)") (class "Default")
      (node (ref "E5") (pin "5") (pinfunction "5_5") (pintype "bidirectional"))
    )
    (net (code "96") (name "unconnected-(E6-Pad4)") (class "Default")
      (node (ref "E6") (pin "4") (pinfunction "4_4") (pintype "bidirectional"))
    )
    (net (code "97") (name "unconnected-(E6-Pad5)") (class "Default")
      (node (ref "E6") (pin "5") (pinfunction "5_5") (pintype "bidirectional"))
    )
    (net (code "98") (name "unconnected-(E7-Pad4)") (class "Default")
      (node (ref "E7") (pin "4") (pinfunction "4_4") (pintype "bidirectional"))
    )
    (net (code "99") (name "unconnected-(E7-Pad5)") (class "Default")
      (node (ref "E7") (pin "5") (pinfunction "5_5") (pintype "bidirectional"))
    )
    (net (code "100") (name "unconnected-(E8-Pad4)") (class "Default")
      (node (ref "E8") (pin "4") (pinfunction "4_4") (pintype "bidirectional"))
    )
    (net (code "101") (name "unconnected-(E8-Pad5)") (class "Default")
      (node (ref "E8") (pin "5") (pinfunction "5_5") (pintype "bidirectional"))
    )
    (net (code "102") (name "unconnected-(E9-Pad4)") (class "Default")
      (node (ref "E9") (pin "4") (pinfunction "4_4") (pintype "bidirectional"))
    )
    (net (code "103") (name "unconnected-(E9-Pad5)") (class "Default")
      (node (ref "E9") (pin "5") (pinfunction "5_5") (pintype "bidirectional"))
    )
    (net (code "104") (name "unconnected-(E10-Pad4)") (class "Default")
      (node (ref "E10") (pin "4") (pinfunction "4_4") (pintype "bidirectional"))
    )
    (net (code "105") (name "unconnected-(E10-Pad5)") (class "Default")
      (node (ref "E10") (pin "5") (pinfunction "5_5") (pintype "bidirectional"))
    )
    (net (code "106") (name "unconnected-(E11-Pad4)") (class "Default")
      (node (ref "E11") (pin "4") (pinfunction "4_4") (pintype "bidirectional"))
    )
    (net (code "107") (name "unconnected-(E11-Pad5)") (class "Default")
      (node (ref "E11") (pin "5") (pinfunction "5_5") (pintype "bidirectional"))
    )
    (net (code "108") (name "unconnected-(E12-Pad4)") (class "Default")
      (node (ref "E12") (pin "4") (pinfunction "4_4") (pintype "bidirectional"))
    )
    (net (code "109") (name "unconnected-(E12-Pad5)") (class "Default")
      (node (ref "E12") (pin "5") (pinfunction "5_5") (pintype "bidirectional"))
    )
    (net (code "110") (name "unconnected-(E13-Pad4)") (class "Default")
      (node (ref "E13") (pin "4") (pinfunction "4_4") (pintype "bidirectional"))
    )
    (net (code "111") (name "unconnected-(E13-Pad5)") (class "Default")
      (node (ref "E13") (pin "5") (pinfunction "5_5") (pintype "bidirectional"))
    )
    (net (code "112") (name "unconnected-(E14-Pad4)") (class "Default")
      (node (ref "E14") (pin "4") (pinfunction "4_4") (pintype "bidirectional"))
    )
    (net (code "113") (name "unconnected-(E14-Pad5)") (class "Default")
      (node (ref "E14") (pin "5") (pinfunction "5_5") (pintype "bidirectional"))
    )
    (net (code "114") (name "unconnected-(E15-Pad4)") (class "Default")
      (node (ref "E15") (pin "4") (pinfunction "4_4") (pintype "bidirectional"))
    )
    (net (code "115") (name "unconnected-(E15-Pad5)") (class "Default")
      (node (ref "E15") (pin "5") (pinfunction "5_5") (pintype "bidirectional"))
    )
    (net (code "116") (name "unconnected-(E16-Pad4)") (class "Default")
      (node (ref "E16") (pin "4") (pinfunction "4_4") (pintype "bidirectional"))
    )
    (net (code "117") (name "unconnected-(E16-Pad5)") (class "Default")
      (node (ref "E16") (pin "5") (pinfunction "5_5") (pintype "bidirectional"))
    )
    (net (code "118") (name "unconnected-(E17-Pad4)") (class "Default")
      (node (ref "E17") (pin "4") (pinfunction "4_4") (pintype "bidirectional"))
    )
    (net (code "119") (name "unconnected-(E17-Pad5)") (class "Default")
      (node (ref "E17") (pin "5") (pinfunction "5_5") (pintype "bidirectional"))
    )
    (net (code "120") (name "unconnected-(E18-Pad4)") (class "Default")
      (node (ref "E18") (pin "4") (pinfunction "4_4") (pintype "bidirectional"))
    )
    (net (code "121") (name "unconnected-(E18-Pad5)") (class "Default")
      (node (ref "E18") (pin "5") (pinfunction "5_5") (pintype "bidirectional"))
    )
    (net (code "122") (name "unconnected-(E19-Pad4)") (class "Default")
      (node (ref "E19") (pin "4") (pinfunction "4_4") (pintype "bidirectional"))
    )
    (net (code "123") (name "unconnected-(E19-Pad5)") (class "Default")
      (node (ref "E19") (pin "5") (pinfunction "5_5") (pintype "bidirectional"))
    )
    (net (code "124") (name "unconnected-(E20-Pad4)") (class "Default")
      (node (ref "E20") (pin "4") (pinfunction "4_4") (pintype "bidirectional"))
    )
    (net (code "125") (name "unconnected-(E20-Pad5)") (class "Default")
      (node (ref "E20") (pin "5") (pinfunction "5_5") (pintype "bidirectional"))
    )
    (net (code "126") (name "unconnected-(U$1-3V3-Pad1)") (class "Default")
      (node (ref "U$1") (pin "1") (pinfunction "3V3_1") (pintype "bidirectional"))
    )
    (net (code "127") (name "unconnected-(U$1-3V3-Pad17)") (class "Default")
      (node (ref "U$1") (pin "17") (pinfunction "3V3_17") (pintype "bidirectional"))
    )
    (net (code "128") (name "unconnected-(U$1-5V-Pad4)") (class "Default")
      (node (ref "U$1") (pin "4") (pinfunction "5V_4") (pintype "bidirectional"))
    )
    (net (code "129") (name "unconnected-(U$1-GPIO0,I2C0_SDA-Pad3)") (class "Default")
      (node (ref "U$1") (pin "3") (pinfunction "GPIO0,I2C0_SDA_3") (pintype "bidirectional"))
    )
    (net (code "130") (name "unconnected-(U$1-GPIO1,I2C0_SCL-Pad5)") (class "Default")
      (node (ref "U$1") (pin "5") (pinfunction "GPIO1,I2C0_SCL_5") (pintype "bidirectional"))
    )
    (net (code "131") (name "unconnected-(U$1-GPIO4,GPCLK0-Pad7)") (class "Default")
      (node (ref "U$1") (pin "7") (pinfunction "GPIO4,GPCLK0_7") (pintype "bidirectional"))
    )
    (net (code "132") (name "unconnected-(U$1-GPIO7,SPI0_CE1-Pad26)") (class "Default")
      (node (ref "U$1") (pin "26") (pinfunction "GPIO7,SPI0_CE1_26") (pintype "bidirectional"))
    )
    (net (code "133") (name "unconnected-(U$1-GPIO8,SPI0_CE0-Pad24)") (class "Default")
      (node (ref "U$1") (pin "24") (pinfunction "GPIO8,SPI0_CE0_24") (pintype "bidirectional"))
    )
    (net (code "134") (name "unconnected-(U$1-GPIO9_MISO-Pad21)") (class "Default")
      (node (ref "U$1") (pin "21") (pinfunction "GPIO9_MISO_21") (pintype "bidirectional"))
    )
    (net (code "135") (name "unconnected-(U$1-GPIO10_MOSI-Pad19)") (class "Default")
      (node (ref "U$1") (pin "19") (pinfunction "GPIO10_MOSI_19") (pintype "bidirectional"))
    )
    (net (code "136") (name "unconnected-(U$1-GPIO11_SCLK-Pad23)") (class "Default")
      (node (ref "U$1") (pin "23") (pinfunction "GPIO11_SCLK_23") (pintype "bidirectional"))
    )
    (net (code "137") (name "unconnected-(U$1-GPIO18-Pad12)") (class "Default")
      (node (ref "U$1") (pin "12") (pinfunction "GPIO18_12") (pintype "bidirectional"))
    )
    (net (code "138") (name "unconnected-(U$1-GPIO21-Pad13)") (class "Default")
      (node (ref "U$1") (pin "13") (pinfunction "GPIO21_13") (pintype "bidirectional"))
    )
    (net (code "139") (name "unconnected-(U$1-GPIO22-Pad15)") (class "Default")
      (node (ref "U$1") (pin "15") (pinfunction "GPIO22_15") (pintype "bidirectional"))
    )
    (net (code "140") (name "unconnected-(U$1-GPIO23-Pad16)") (class "Default")
      (node (ref "U$1") (pin "16") (pinfunction "GPIO23_16") (pintype "bidirectional"))
    )
    (net (code "141") (name "unconnected-(U$1-GPIO24-Pad18)") (class "Default")
      (node (ref "U$1") (pin "18") (pinfunction "GPIO24_18") (pintype "bidirectional"))
    )
    (net (code "142") (name "unconnected-(U$1-GPIO25-Pad22)") (class "Default")
      (node (ref "U$1") (pin "22") (pinfunction "GPIO25_22") (pintype "bidirectional"))
    )
  )
)
